# robot_systems.net
KiCad netlist of a schematic drawn in EAGLE
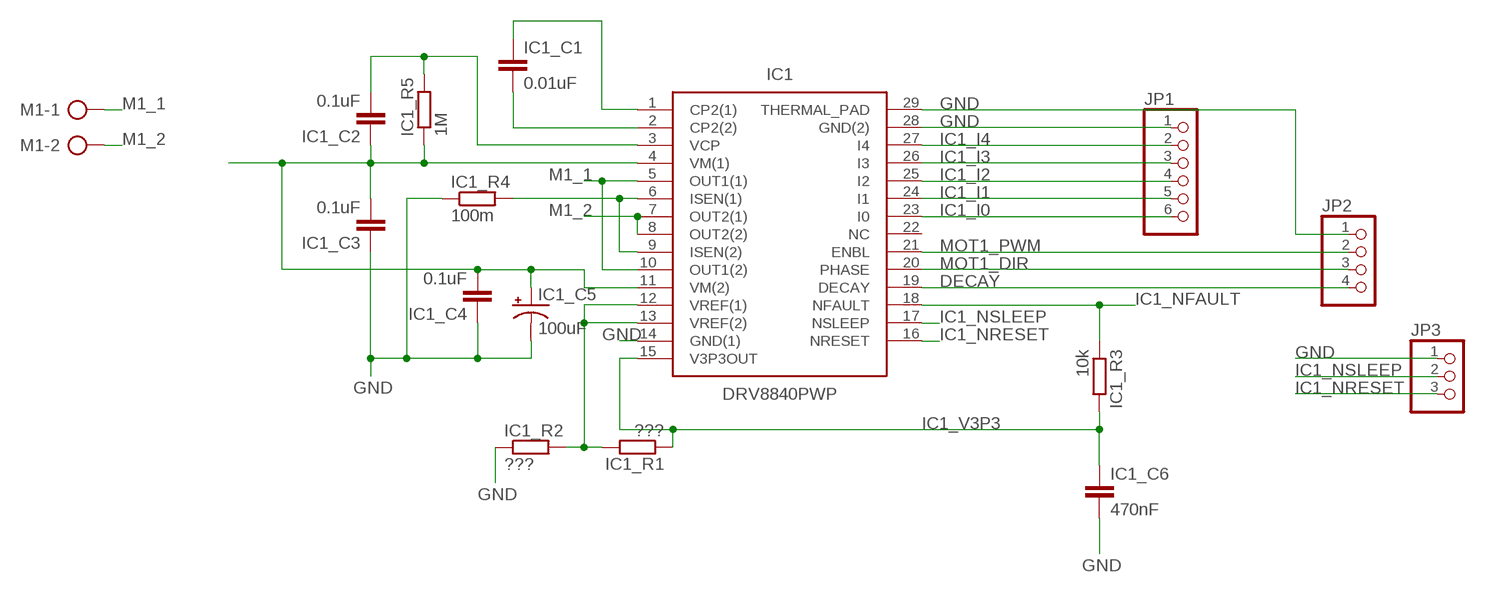
[diagram p0: schematic, sheet 1]

(export (version "E")
  (design (tool "Eeschema 10.0.6"))
  (components
    (comp (ref "IC1")
      (value "DRV8840PWP")
      (footprint "eagle-import:SOP65P640X120-29N")
      (fields (field (name "RS_PART_NUMBER") "7385440"))
      (libsource (lib "eagle-import") (part "DRV8840PWP"))
    )
    (comp (ref "IC1_C1")
      (value "0.01uF")
      (footprint "eagle-import:C0603")
      (libsource (lib "eagle-import") (part "C-EUC0603"))
    )
    (comp (ref "IC1_C2")
      (value "0.1uF")
      (footprint "eagle-import:0805")
      (libsource (lib "eagle-import") (part "CAP0805"))
    )
    (comp (ref "IC1_C3")
      (value "0.1uF")
      (footprint "eagle-import:0805")
      (libsource (lib "eagle-import") (part "CAP0805"))
    )
    (comp (ref "IC1_C4")
      (value "0.1uF")
      (footprint "eagle-import:1206")
      (libsource (lib "eagle-import") (part "CAP1206"))
    )
    (comp (ref "IC1_C5")
      (value "100uF")
      (footprint "eagle-import:EIA7343")
      (libsource (lib "eagle-import") (part "CAP_POL7343"))
    )
    (comp (ref "IC1_C6")
      (value "470nF")
      (footprint "eagle-import:C0603")
      (libsource (lib "eagle-import") (part "C-EUC0603"))
    )
    (comp (ref "IC1_R1")
      (value "???")
      (footprint "eagle-import:0204_5")
      (libsource (lib "eagle-import") (part "resistor_R-EU_0204/5"))
    )
    (comp (ref "IC1_R2")
      (value "???")
      (footprint "eagle-import:0204_5")
      (libsource (lib "eagle-import") (part "resistor_R-EU_0204/5"))
    )
    (comp (ref "IC1_R3")
      (value "10k")
      (footprint "eagle-import:R2010")
      (libsource (lib "eagle-import") (part "R-EU_R2010"))
    )
    (comp (ref "IC1_R4")
      (value "100m")
      (footprint "eagle-import:R2512")
      (libsource (lib "eagle-import") (part "R-EU_R2512"))
    )
    (comp (ref "IC1_R5")
      (value "1M")
      (footprint "eagle-import:R0603")
      (libsource (lib "eagle-import") (part "R-EU_R0603"))
    )
    (comp (ref "JP1")
      (value "PINHD-1X6")
      (footprint "eagle-import:1X06")
      (libsource (lib "eagle-import") (part "PINHD-1X6"))
    )
    (comp (ref "JP2")
      (value "PINHD-1X4")
      (footprint "eagle-import:1X04")
      (libsource (lib "eagle-import") (part "PINHD-1X4"))
    )
    (comp (ref "JP3")
      (value "PINHD-1X3")
      (footprint "eagle-import:1X03")
      (libsource (lib "eagle-import") (part "PINHD-1X3"))
    )
    (comp (ref "M1")
      (value "AK500/2")
      (footprint "eagle-import:AK500_2")
      (libsource (lib "eagle-import") (part "AK500/2"))
    )
  )
  (nets
    (net (code "1") (name "/DECAY") (class "Default")
      (node (ref "IC1") (pin "19") (pinfunction "DECAY_19") (pintype "passive"))
      (node (ref "JP2") (pin "4") (pinfunction "4_4") (pintype "passive"))
    )
    (net (code "2") (name "/GND") (class "Default")
      (node (ref "IC1") (pin "14") (pinfunction "GND(1)_14") (pintype "passive"))
      (node (ref "IC1") (pin "28") (pinfunction "GND(2)_28") (pintype "passive"))
      (node (ref "IC1") (pin "29") (pinfunction "THERMAL_PAD_29") (pintype "passive"))
      (node (ref "IC1_C3") (pin "1") (pinfunction "1_1") (pintype "passive"))
      (node (ref "IC1_C4") (pin "1") (pinfunction "1_1") (pintype "passive"))
      (node (ref "IC1_C5") (pin "C") (pinfunction "-_C") (pintype "passive"))
      (node (ref "IC1_C6") (pin "2") (pinfunction "2_2") (pintype "passive"))
      (node (ref "IC1_R2") (pin "1") (pinfunction "1_1") (pintype "passive"))
      (node (ref "IC1_R4") (pin "1") (pinfunction "1_1") (pintype "passive"))
      (node (ref "JP1") (pin "1") (pinfunction "1_1") (pintype "passive"))
      (node (ref "JP2") (pin "1") (pinfunction "1_1") (pintype "passive"))
      (node (ref "JP3") (pin "1") (pinfunction "1_1") (pintype "passive"))
    )
    (net (code "3") (name "/IC1_I0") (class "Default")
      (node (ref "IC1") (pin "23") (pinfunction "I0_23") (pintype "passive"))
      (node (ref "JP1") (pin "6") (pinfunction "6_6") (pintype "passive"))
    )
    (net (code "4") (name "/IC1_I1") (class "Default")
      (node (ref "IC1") (pin "24") (pinfunction "I1_24") (pintype "passive"))
      (node (ref "JP1") (pin "5") (pinfunction "5_5") (pintype "passive"))
    )
    (net (code "5") (name "/IC1_I2") (class "Default")
      (node (ref "IC1") (pin "25") (pinfunction "I2_25") (pintype "passive"))
      (node (ref "JP1") (pin "4") (pinfunction "4_4") (pintype "passive"))
    )
    (net (code "6") (name "/IC1_I3") (class "Default")
      (node (ref "IC1") (pin "26") (pinfunction "I3_26") (pintype "passive"))
      (node (ref "JP1") (pin "3") (pinfunction "3_3") (pintype "passive"))
    )
    (net (code "7") (name "/IC1_I4") (class "Default")
      (node (ref "IC1") (pin "27") (pinfunction "I4_27") (pintype "passive"))
      (node (ref "JP1") (pin "2") (pinfunction "2_2") (pintype "passive"))
    )
    (net (code "8") (name "/IC1_NFAULT") (class "Default")
      (node (ref "IC1") (pin "18") (pinfunction "NFAULT_18") (pintype "passive"))
      (node (ref "IC1_R3") (pin "1") (pinfunction "1_1") (pintype "passive"))
    )
    (net (code "9") (name "/IC1_NRESET") (class "Default")
      (node (ref "IC1") (pin "16") (pinfunction "NRESET_16") (pintype "passive"))
      (node (ref "JP3") (pin "3") (pinfunction "3_3") (pintype "passive"))
    )
    (net (code "10") (name "/IC1_NSLEEP") (class "Default")
      (node (ref "IC1") (pin "17") (pinfunction "NSLEEP_17") (pintype "passive"))
      (node (ref "JP3") (pin "2") (pinfunction "2_2") (pintype "passive"))
    )
    (net (code "11") (name "/IC1_V3P3") (class "Default")
      (node (ref "IC1") (pin "15") (pinfunction "V3P3OUT_15") (pintype "passive"))
      (node (ref "IC1_C6") (pin "1") (pinfunction "1_1") (pintype "passive"))
      (node (ref "IC1_R1") (pin "1") (pinfunction "1_1") (pintype "passive"))
      (node (ref "IC1_R3") (pin "2") (pinfunction "2_2") (pintype "passive"))
    )
    (net (code "12") (name "/M1_1") (class "Default")
      (node (ref "IC1") (pin "10") (pinfunction "OUT1(2)_10") (pintype "passive"))
      (node (ref "IC1") (pin "5") (pinfunction "OUT1(1)_5") (pintype "passive"))
      (node (ref "M1") (pin "1") (pinfunction "KL_1") (pintype "passive"))
    )
    (net (code "13") (name "/M1_2") (class "Default")
      (node (ref "IC1") (pin "7") (pinfunction "OUT2(1)_7") (pintype "passive"))
      (node (ref "IC1") (pin "8") (pinfunction "OUT2(2)_8") (pintype "passive"))
      (node (ref "M1") (pin "2") (pinfunction "KL_2") (pintype "passive"))
    )
    (net (code "14") (name "/MOT1_DIR") (class "Default")
      (node (ref "IC1") (pin "20") (pinfunction "PHASE_20") (pintype "passive"))
      (node (ref "JP2") (pin "3") (pinfunction "3_3") (pintype "passive"))
    )
    (net (code "15") (name "/MOT1_PWM") (class "Default")
      (node (ref "IC1") (pin "21") (pinfunction "ENBL_21") (pintype "passive"))
      (node (ref "JP2") (pin "2") (pinfunction "2_2") (pintype "passive"))
    )
    (net (code "16") (name "Net-(IC1-CP2(1))") (class "Default")
      (node (ref "IC1") (pin "1") (pinfunction "CP2(1)_1") (pintype "passive"))
      (node (ref "IC1_C1") (pin "1") (pinfunction "1_1") (pintype "passive"))
    )
    (net (code "17") (name "Net-(IC1-CP2(2))") (class "Default")
      (node (ref "IC1") (pin "2") (pinfunction "CP2(2)_2") (pintype "passive"))
      (node (ref "IC1_C1") (pin "2") (pinfunction "2_2") (pintype "passive"))
    )
    (net (code "18") (name "Net-(IC1-ISEN(1))") (class "Default")
      (node (ref "IC1") (pin "6") (pinfunction "ISEN(1)_6") (pintype "passive"))
      (node (ref "IC1") (pin "9") (pinfunction "ISEN(2)_9") (pintype "passive"))
      (node (ref "IC1_R4") (pin "2") (pinfunction "2_2") (pintype "passive"))
    )
    (net (code "19") (name "Net-(IC1-VCP)") (class "Default")
      (node (ref "IC1") (pin "3") (pinfunction "VCP_3") (pintype "passive"))
      (node (ref "IC1_C2") (pin "2") (pinfunction "2_2") (pintype "passive"))
      (node (ref "IC1_R5") (pin "2") (pinfunction "2_2") (pintype "passive"))
    )
    (net (code "20") (name "Net-(IC1-VM(1))") (class "Default")
      (node (ref "IC1") (pin "11") (pinfunction "VM(2)_11") (pintype "passive"))
      (node (ref "IC1") (pin "4") (pinfunction "VM(1)_4") (pintype "passive"))
      (node (ref "IC1_C2") (pin "1") (pinfunction "1_1") (pintype "passive"))
      (node (ref "IC1_C3") (pin "2") (pinfunction "2_2") (pintype "passive"))
      (node (ref "IC1_C4") (pin "2") (pinfunction "2_2") (pintype "passive"))
      (node (ref "IC1_C5") (pin "A") (pinfunction "+_A") (pintype "passive"))
      (node (ref "IC1_R5") (pin "1") (pinfunction "1_1") (pintype "passive"))
    )
    (net (code "21") (name "Net-(IC1-VREF(1))") (class "Default")
      (node (ref "IC1") (pin "12") (pinfunction "VREF(1)_12") (pintype "passive"))
      (node (ref "IC1") (pin "13") (pinfunction "VREF(2)_13") (pintype "passive"))
      (node (ref "IC1_R1") (pin "2") (pinfunction "2_2") (pintype "passive"))
      (node (ref "IC1_R2") (pin "2") (pinfunction "2_2") (pintype "passive"))
    )
    (net (code "22") (name "unconnected-(IC1-NC-Pad22)") (class "Default")
      (node (ref "IC1") (pin "22") (pinfunction "NC_22") (pintype "no_connect"))
    )
  )
)
